# Display.net
KiCad netlist of a schematic drawn in Altium Designer
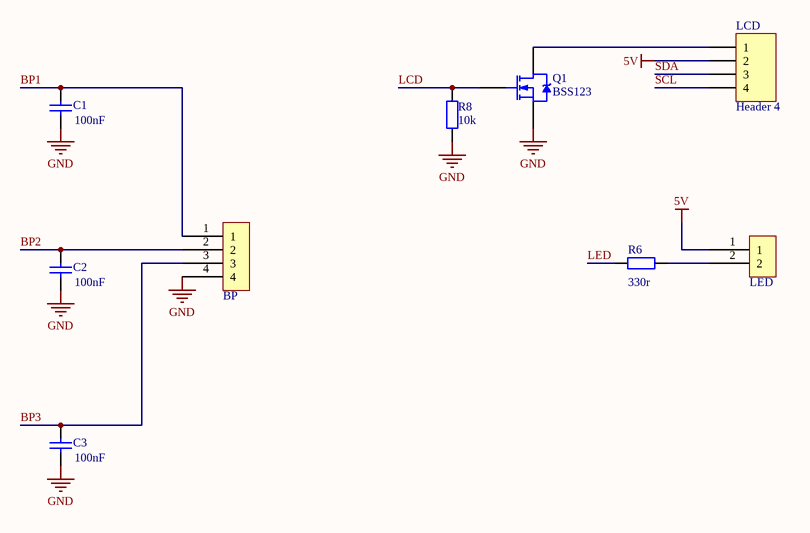
[diagram p0: Display.SchDoc]

(export (version "E")
  (design (tool "Eeschema 10.0.6"))
  (components
    (comp (ref "BP")
      (value "Bornier_4_vis")
      (footprint "282834-4")
      (description "Bornier fil-à-carte, 2.54 mm, 4 Voies, 30 AWG, 16 AWG, 1.4 mm², Par vis")
      (fields (field (name "VOLTAGE") "150V"))
      (libsource (lib "MGLib_v2") (part "Bornier_4_vis"))
    )
    (comp (ref "C1")
      (value "100nF")
      (footprint "0805-C")
      (description "Condensateur céramique multicouche CMS, 0.1 µF, 50 V, 0805 [2012 Metric], ± 10%, X7R")
      (fields (field (name "VOLTAGE") "50V"))
      (libsource (lib "GEII1") (part "Cap_np"))
    )
    (comp (ref "C2")
      (value "100nF")
      (footprint "0805-C")
      (description "Condensateur céramique multicouche CMS, 0.1 µF, 50 V, 0805 [2012 Metric], ± 10%, X7R")
      (fields (field (name "VOLTAGE") "50V"))
      (libsource (lib "MGLib_v2") (part "Cap_np"))
    )
    (comp (ref "C3")
      (value "100nF")
      (footprint "0805-C")
      (description "Condensateur céramique multicouche CMS, 0.1 µF, 50 V, 0805 [2012 Metric], ± 10%, X7R")
      (fields (field (name "VOLTAGE") "50V"))
      (libsource (lib "MGLib_v2") (part "Cap_np"))
    )
    (comp (ref "LCD")
      (value "Header 4")
      (footprint "HDR1X4")
      (description "Header mâle, Carte-à-carte, 2.54 mm, 1 Rangée(s), 10 Contact(s), Traversant, droit, Série 2211S")
      (libsource (lib "Miscellaneous Connectors") (part "Header 4"))
    )
    (comp (ref "LED")
      (value "Bornier_2_vis")
      (footprint "282834-2")
      (description "Bornier fil-à-carte, 2.54 mm, 2 Voies, 30 AWG, 16 AWG, 1.4 mm², Par vis")
      (fields (field (name "VOLTAGE") "150V"))
      (libsource (lib "MGLib_v2") (part "Bornier_2_vis"))
    )
    (comp (ref "Q1")
      (value "BSS123")
      (footprint "SOT23-3")
      (description "MOSFET de puissance, Canal N, 100 V, 170 mA, 1.2 ohm, SOT-23, Montage en surface")
      (fields (field (name "VOLTAGE") "100V"))
      (libsource (lib "MGLib") (part "2N7000"))
    )
    (comp (ref "R6")
      (value "330r")
      (footprint "0805-R")
      (description "Résistance à puce CMS, Couche épaisse, 330 ohm, ± 1%, 125 mW, 0805 [2012 Metric], Couche épaisse")
      (fields (field (name "VOLTAGE") "150V"))
      (libsource (lib "GEII1") (part "Res"))
    )
    (comp (ref "R8")
      (value "10k")
      (footprint "0805-R")
      (description "Résistance à puce CMS, 10 kohm, ± 1%, 250 mW, 0805 [2012 Metric], Couche épaisse, Haute puissance")
      (fields (field (name "VOLTAGE") "150V"))
      (libsource (lib "MGLib_v2") (part "Res"))
    )
  )
  (nets
    (net (code "1") (name "/BP1") (class "Default")
      (node (ref "BP") (pin "1") (pinfunction "1_1") (pintype "passive"))
      (node (ref "C1") (pin "2") (pinfunction "2_2") (pintype "passive"))
    )
    (net (code "2") (name "/BP2") (class "Default")
      (node (ref "BP") (pin "2") (pinfunction "2_2") (pintype "passive"))
      (node (ref "C2") (pin "2") (pinfunction "2_2") (pintype "passive"))
    )
    (net (code "3") (name "/BP3") (class "Default")
      (node (ref "BP") (pin "3") (pinfunction "3_3") (pintype "passive"))
      (node (ref "C3") (pin "2") (pinfunction "2_2") (pintype "passive"))
    )
    (net (code "4") (name "/LCD") (class "Default")
      (node (ref "Q1") (pin "1") (pinfunction "G_1") (pintype "passive"))
      (node (ref "R8") (pin "2") (pinfunction "2_2") (pintype "passive"))
    )
    (net (code "5") (name "/LED") (class "Default")
      (node (ref "R6") (pin "1") (pinfunction "1_1") (pintype "passive"))
    )
    (net (code "6") (name "/SCL") (class "Default")
      (node (ref "LCD") (pin "4") (pinfunction "4_4") (pintype "passive"))
    )
    (net (code "7") (name "/SDA") (class "Default")
      (node (ref "LCD") (pin "3") (pinfunction "3_3") (pintype "passive"))
    )
    (net (code "8") (name "5V") (class "Default")
      (node (ref "LCD") (pin "2") (pinfunction "2_2") (pintype "passive"))
      (node (ref "LED") (pin "1") (pinfunction "1_1") (pintype "passive"))
    )
    (net (code "9") (name "GND") (class "Default")
      (node (ref "BP") (pin "4") (pinfunction "4_4") (pintype "passive"))
      (node (ref "C1") (pin "1") (pinfunction "1_1") (pintype "passive"))
      (node (ref "C2") (pin "1") (pinfunction "1_1") (pintype "passive"))
      (node (ref "C3") (pin "1") (pinfunction "1_1") (pintype "passive"))
      (node (ref "Q1") (pin "2") (pinfunction "S_2") (pintype "passive"))
      (node (ref "R8") (pin "1") (pinfunction "1_1") (pintype "passive"))
    )
    (net (code "10") (name "Net-(LED-Pad2)") (class "Default")
      (node (ref "LED") (pin "2") (pinfunction "2_2") (pintype "passive"))
      (node (ref "R6") (pin "2") (pinfunction "2_2") (pintype "passive"))
    )
    (net (code "11") (name "Net-(Q1-D)") (class "Default")
      (node (ref "LCD") (pin "1") (pinfunction "1_1") (pintype "passive"))
      (node (ref "Q1") (pin "3") (pinfunction "D_3") (pintype "passive"))
    )
  )
)
